# Buzzer.net
KiCad netlist of a schematic drawn in Altium Designer
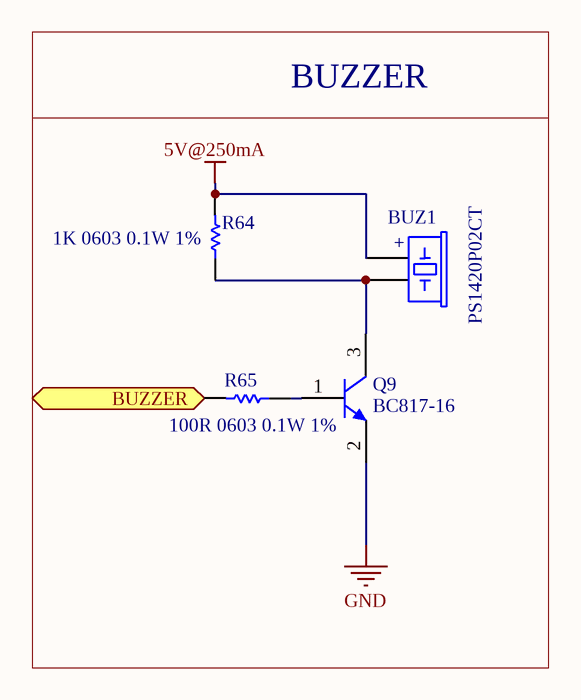
[diagram p0: Buzzer.SchDoc]

(export (version "E")
  (design (tool "Eeschema 10.0.6"))
  (components
    (comp (ref "BUZ1")
      (value "PS1420P02CT")
      (footprint "PCB-snegfq1spk96rguke62s-1")
      (description "BUZZER, PIEZO, 70DB, 14MM; Transducer Function: Buzzer; Tones: Low Frequency; Supp")
      (libsource (lib "CommunityVault") (part "CMP-0cb8c507bf0ed37f-8"))
    )
    (comp (ref "Q9")
      (value "BC817-16")
      (footprint "PCB-856332-1")
      (description "TRANS NPN 45V 500mA SMD SOT23-3")
      (libsource (lib "CommunityVault") (part "CMP-856332-3"))
    )
    (comp (ref "R64")
      (value "1K 0603 0.1W 1%")
      (footprint "RESC1609X55X30ML10T20")
      (fields (field (name "MANUFACTURER PART NUMBER") "CR0603-FX-1001ELF"))
      (libsource (lib "CommunityVault") (part "CMP-a61f6f36030f79d8-4"))
    )
    (comp (ref "R65")
      (value "100R 0603 0.1W 1%")
      (footprint "RESC1609X55X30ML10T20")
      (fields (field (name "MANUFACTURER PART NUMBER") "CR0603-FX-1001ELF"))
      (libsource (lib "CommunityVault") (part "CMP-a61f6f36030f79d8-4"))
    )
  )
  (nets
    (net (code "1") (name "/BUZZER") (class "Default")
      (node (ref "R65") (pin "2") (pinfunction "2_2") (pintype "passive"))
    )
    (net (code "2") (name "5V@250mA") (class "Default")
      (node (ref "BUZ1") (pin "1") (pinfunction "+_1") (pintype "passive"))
      (node (ref "R64") (pin "2") (pinfunction "2_2") (pintype "passive"))
    )
    (net (code "3") (name "GND") (class "Default")
      (node (ref "Q9") (pin "2") (pinfunction "E_2") (pintype "passive"))
    )
    (net (code "4") (name "Net-(BUZ1--)") (class "Default")
      (node (ref "BUZ1") (pin "2") (pinfunction "-_2") (pintype "passive"))
      (node (ref "Q9") (pin "3") (pinfunction "C_3") (pintype "passive"))
      (node (ref "R64") (pin "1") (pinfunction "1_1") (pintype "passive"))
    )
    (net (code "5") (name "Net-(Q9-B)") (class "Default")
      (node (ref "Q9") (pin "1") (pinfunction "B_1") (pintype "passive"))
      (node (ref "R65") (pin "1") (pinfunction "1_1") (pintype "passive"))
    )
  )
)
